# greenhouse_MA_2.net
KiCad netlist of a schematic drawn in Altium Designer
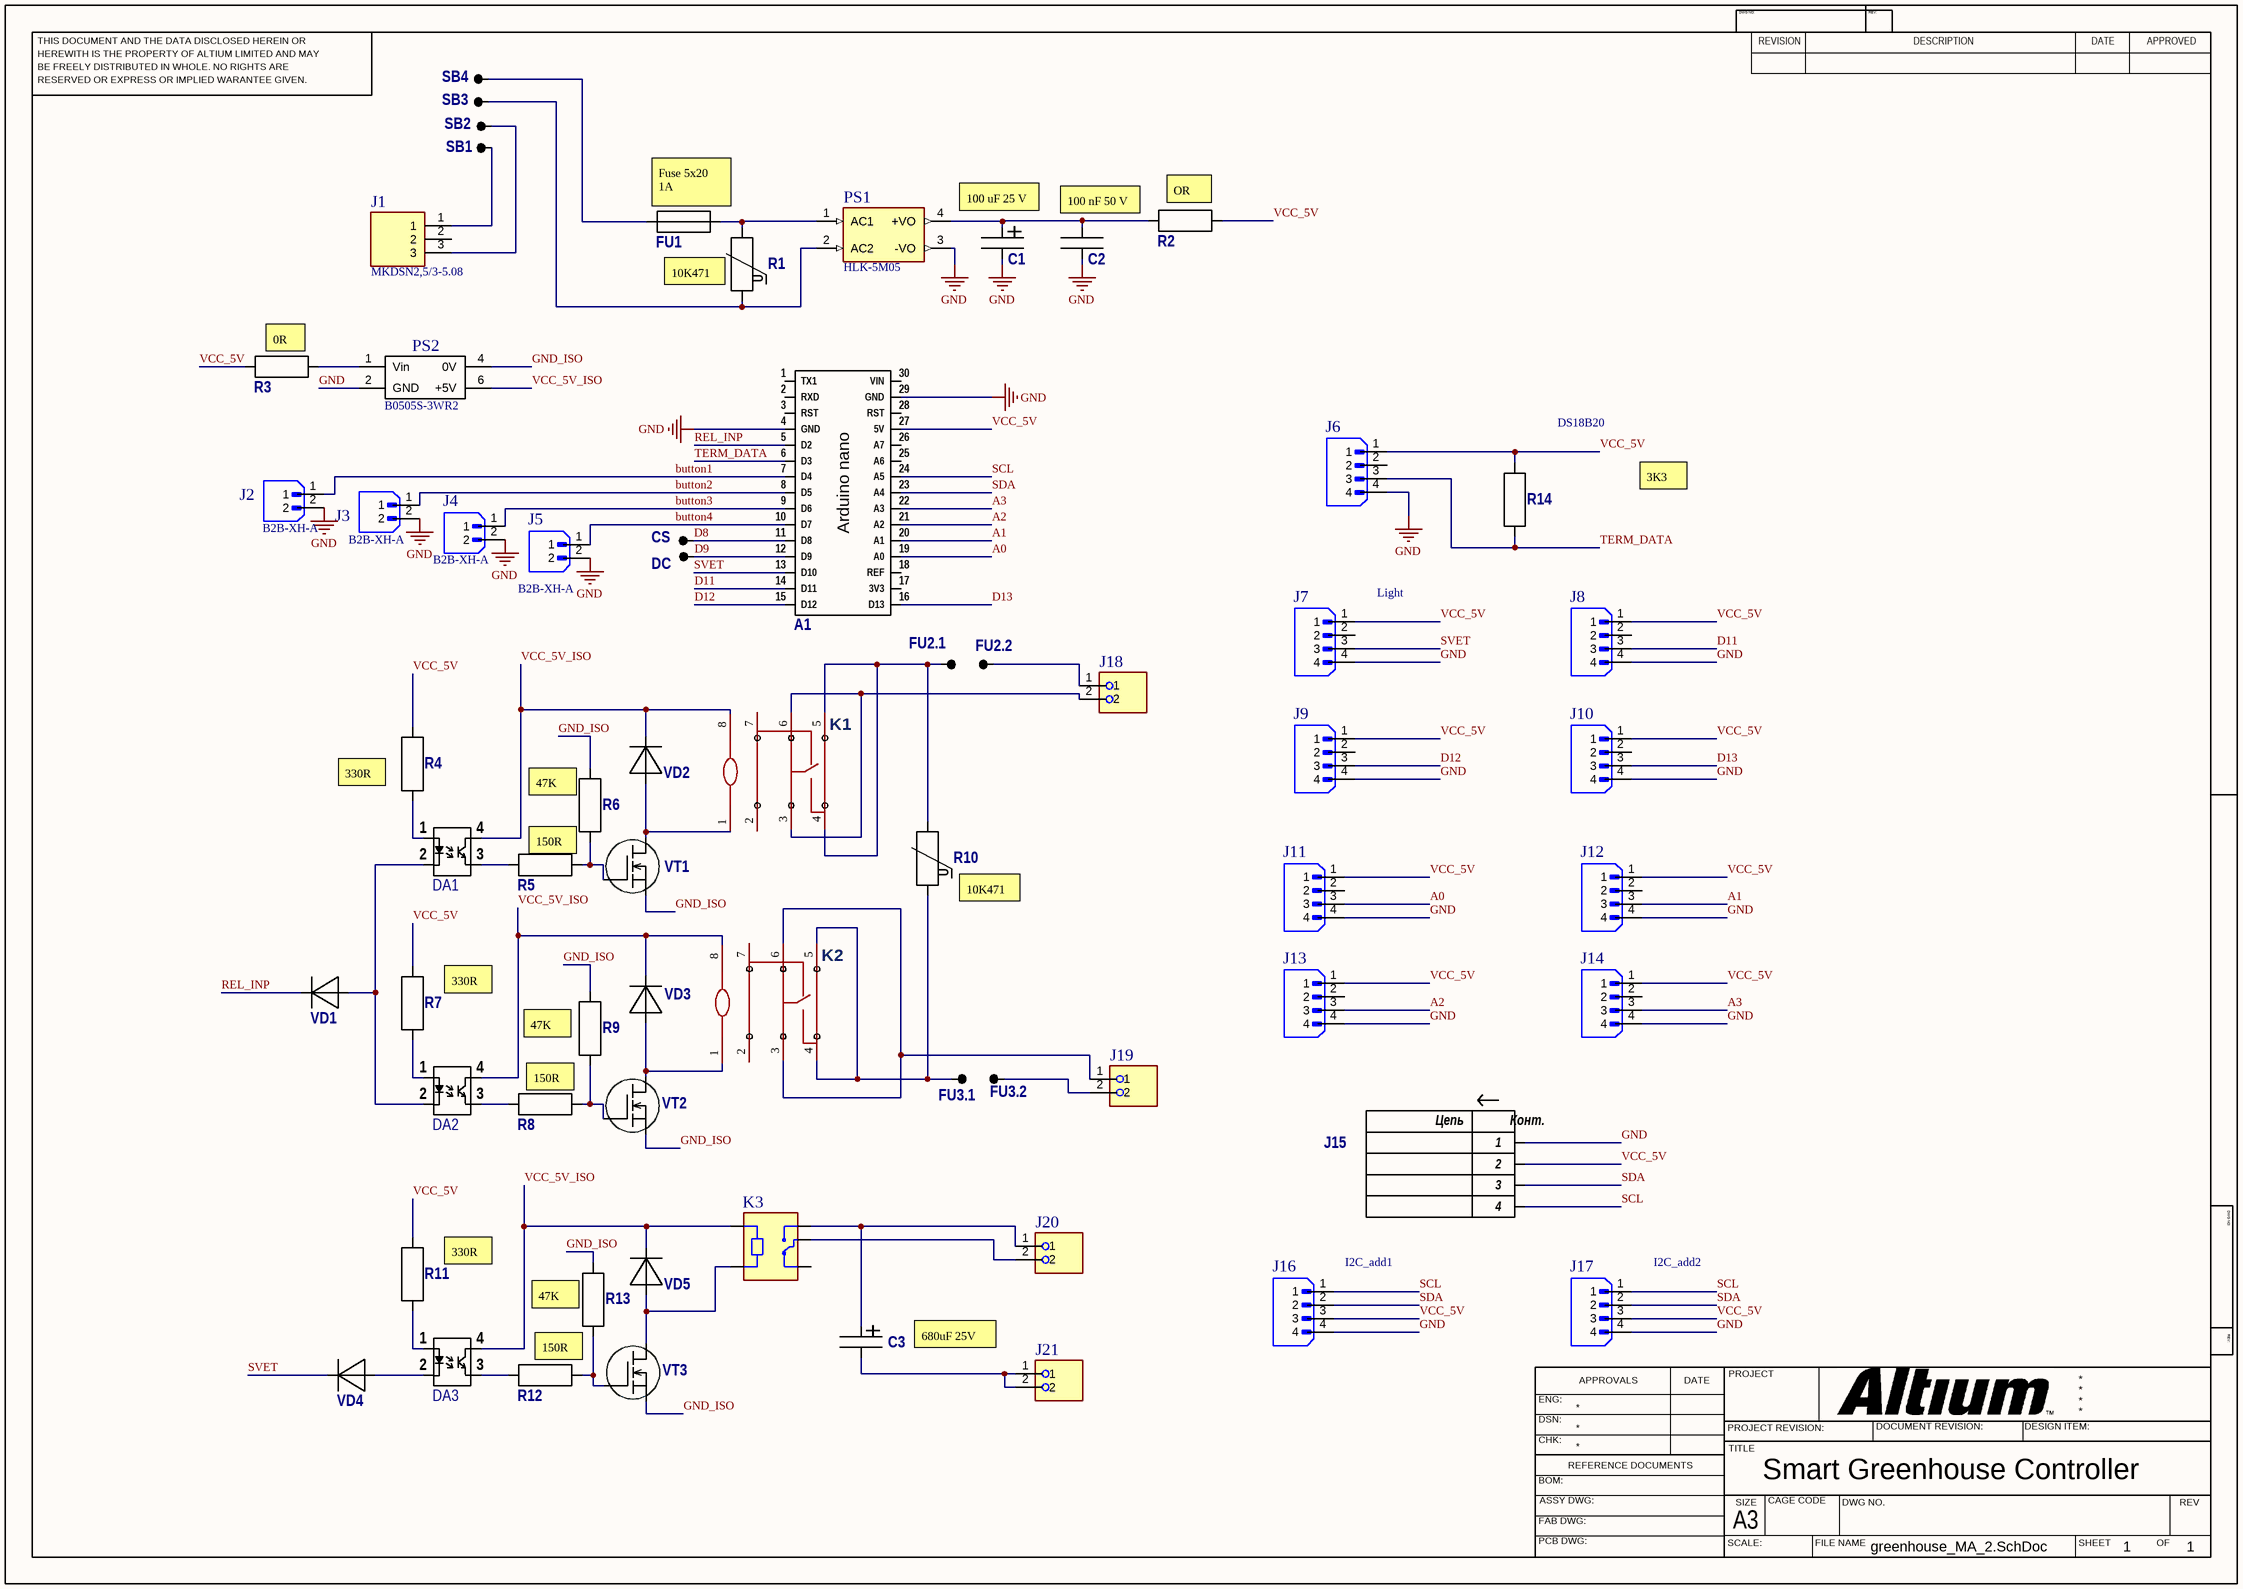
[diagram p0: greenhouse_MA_2.SchDoc]

(export (version "E")
  (design (tool "Eeschema 10.0.6"))
  (components
    (comp (ref "A1")
      (value "Arduino Nano")
      (footprint "Arduino nano")
      (libsource (lib "Microcontroller_V3.4_BVI") (part "Arduino Nano"))
    )
    (comp (ref "C1")
      (value "100uF 25V Electrolytic Capacitor THT Radial")
      (footprint "capr- 2.5D6.5H12")
      (description "Конденсатор алюминиевый радиальный")
      (libsource (lib "RLC V7.1_BVI") (part "C Al R"))
    )
    (comp (ref "C2")
      (value "100nF 50V X7R THT 5mm")
      (footprint "C__s 5-d 5.5-t4")
      (description "Конденсатор керамика")
      (libsource (lib "RLC V7.1_BVI") (part "C_Disk"))
    )
    (comp (ref "C3")
      (value "680uF 25V Electrolytic Capacitor THT Radial")
      (footprint "capr- 3.5D8H20")
      (description "Конденсатор алюминиевый радиальный")
      (libsource (lib "RLC V7.1_BVI") (part "C Al R"))
    )
    (comp (ref "CS")
      (value "Отпайка")
      (footprint "Отпайка 0,5")
      (description "Отпайка для проводника")
      (libsource (lib "RLC V7.1_BVI") (part "Отпайка"))
    )
    (comp (ref "DA1")
      (value "Optocoupler EL817 DIP-4")
      (footprint "DIP-4")
      (description "Оптрон выход - транзистор")
      (libsource (lib "Optocoupler V2.2_BVI") (part "EL817"))
    )
    (comp (ref "DA2")
      (value "Optocoupler EL817 DIP-4")
      (footprint "DIP-4")
      (description "Оптрон выход - транзистор")
      (libsource (lib "Optocoupler V2.2_BVI") (part "EL817"))
    )
    (comp (ref "DA3")
      (value "Optocoupler EL817 DIP-4")
      (footprint "DIP-4")
      (description "Оптрон выход - транзистор")
      (libsource (lib "Optocoupler V2.2_BVI") (part "EL817"))
    )
    (comp (ref "DC")
      (value "Отпайка")
      (footprint "Отпайка 0,5")
      (description "Отпайка для проводника")
      (libsource (lib "RLC V7.1_BVI") (part "Отпайка"))
    )
    (comp (ref "FU1")
      (value "1A slow 5x20 mm")
      (footprint "FU_FC-001-N(DH)")
      (description "Предохранитель плавкий с держателем.")
      (libsource (lib "RLC V7.1_BVI") (part "FU + Clip"))
    )
    (comp (ref "FU2.1")
      (value "Отпайка")
      (footprint "Отпайка 1.5")
      (description "Отпайка для проводника")
      (libsource (lib "RLC V7.1_BVI") (part "Отпайка"))
    )
    (comp (ref "FU2.2")
      (value "Отпайка")
      (footprint "Отпайка 1.5")
      (description "Отпайка для проводника")
      (libsource (lib "RLC V7.1_BVI") (part "Отпайка"))
    )
    (comp (ref "FU3.1")
      (value "Отпайка")
      (footprint "Отпайка 1.5")
      (description "Отпайка для проводника")
      (libsource (lib "RLC V7.1_BVI") (part "Отпайка"))
    )
    (comp (ref "FU3.2")
      (value "Отпайка")
      (footprint "Отпайка 1.5")
      (description "Отпайка для проводника")
      (libsource (lib "RLC V7.1_BVI") (part "Отпайка"))
    )
    (comp (ref "J1")
      (value "MKDSN2,5/3-5.08")
      (footprint "PHOENIX_MKDSN2,5/3-5.08")
      (fields (field (name "MF") "Phoenix Contact"))
      (libsource (lib "MKDSN2_5_3-5.08") (part "MKDSN2,5/3-5.08"))
    )
    (comp (ref "J2")
      (value "B2B-XH-A")
      (footprint "JST_B2B-XH-A")
      (fields (field (name "MF") "{'manufacturer': u'JST Sales America Inc.'}"))
      (libsource (lib "B2B-XH-A") (part "B2B-XH-A"))
    )
    (comp (ref "J3")
      (value "B2B-XH-A")
      (footprint "JST_B2B-XH-A")
      (fields (field (name "MF") "{'manufacturer': u'JST Sales America Inc.'}"))
      (libsource (lib "B2B-XH-A") (part "B2B-XH-A"))
    )
    (comp (ref "J4")
      (value "B2B-XH-A")
      (footprint "JST_B2B-XH-A")
      (fields (field (name "MF") "{'manufacturer': u'JST Sales America Inc.'}"))
      (libsource (lib "B2B-XH-A") (part "B2B-XH-A"))
    )
    (comp (ref "J5")
      (value "B2B-XH-A")
      (footprint "JST_B2B-XH-A")
      (fields (field (name "MF") "{'manufacturer': u'JST Sales America Inc.'}"))
      (libsource (lib "B2B-XH-A") (part "B2B-XH-A"))
    )
    (comp (ref "J6")
      (value "JST B4B-XH-A Connector 1x4 2.5mm THT Vertical")
      (footprint "JST_B4B-XH-A")
      (description "Connector Header Through Hole 4 position 0.098 (2.50mm)")
      (fields (field (name "MF") "JST Sales") (field (name "MP") "B4B-XH-A"))
      (libsource (lib "B4B-XH-A") (part "B4B-XH-A"))
    )
    (comp (ref "J7")
      (value "JST B4B-XH-A Connector 1x4 2.5mm THT Vertical")
      (footprint "JST_B4B-XH-A")
      (description "Connector Header Through Hole 4 position 0.098 (2.50mm)")
      (fields (field (name "MF") "JST Sales") (field (name "MP") "B4B-XH-A"))
      (libsource (lib "B4B-XH-A") (part "B4B-XH-A"))
    )
    (comp (ref "J8")
      (value "JST B4B-XH-A Connector 1x4 2.5mm THT Vertical")
      (footprint "JST_B4B-XH-A")
      (description "Connector Header Through Hole 4 position 0.098 (2.50mm)")
      (fields (field (name "MF") "JST Sales") (field (name "MP") "B4B-XH-A"))
      (libsource (lib "B4B-XH-A") (part "B4B-XH-A"))
    )
    (comp (ref "J9")
      (value "JST B4B-XH-A Connector 1x4 2.5mm THT Vertical")
      (footprint "JST_B4B-XH-A")
      (description "Connector Header Through Hole 4 position 0.098 (2.50mm)")
      (fields (field (name "MF") "JST Sales") (field (name "MP") "B4B-XH-A"))
      (libsource (lib "B4B-XH-A") (part "B4B-XH-A"))
    )
    (comp (ref "J10")
      (value "JST B4B-XH-A Connector 1x4 2.5mm THT Vertical")
      (footprint "JST_B4B-XH-A")
      (description "Connector Header Through Hole 4 position 0.098 (2.50mm)")
      (fields (field (name "MF") "JST Sales") (field (name "MP") "B4B-XH-A"))
      (libsource (lib "B4B-XH-A") (part "B4B-XH-A"))
    )
    (comp (ref "J11")
      (value "JST B4B-XH-A Connector 1x4 2.5mm THT Vertical")
      (footprint "JST_B4B-XH-A")
      (description "Connector Header Through Hole 4 position 0.098 (2.50mm)")
      (fields (field (name "MF") "JST Sales") (field (name "MP") "B4B-XH-A"))
      (libsource (lib "B4B-XH-A") (part "B4B-XH-A"))
    )
    (comp (ref "J12")
      (value "JST B4B-XH-A Connector 1x4 2.5mm THT Vertical")
      (footprint "JST_B4B-XH-A")
      (description "Connector Header Through Hole 4 position 0.098 (2.50mm)")
      (fields (field (name "MF") "JST Sales") (field (name "MP") "B4B-XH-A"))
      (libsource (lib "B4B-XH-A") (part "B4B-XH-A"))
    )
    (comp (ref "J13")
      (value "JST B4B-XH-A Connector 1x4 2.5mm THT Vertical")
      (footprint "JST_B4B-XH-A")
      (description "Connector Header Through Hole 4 position 0.098 (2.50mm)")
      (fields (field (name "MF") "JST Sales") (field (name "MP") "B4B-XH-A"))
      (libsource (lib "B4B-XH-A") (part "B4B-XH-A"))
    )
    (comp (ref "J14")
      (value "JST B4B-XH-A Connector 1x4 2.5mm THT Vertical")
      (footprint "JST_B4B-XH-A")
      (description "Connector Header Through Hole 4 position 0.098 (2.50mm)")
      (fields (field (name "MF") "JST Sales") (field (name "MP") "B4B-XH-A"))
      (libsource (lib "B4B-XH-A") (part "B4B-XH-A"))
    )
    (comp (ref "J15")
      (value "Pin Header 1x4 2.54mm Right Angle THT Male")
      (footprint "KLS1-207-1*04 R")
      (description "Разъём штыревой на плату 2.54мм 1х4 pin")
      (libsource (lib "Connectors V8.3_BVI") (part "Штырь 1* 4  (1)"))
    )
    (comp (ref "J16")
      (value "JST B4B-XH-A Connector 1x4 2.5mm THT Vertical")
      (footprint "JST_B4B-XH-A")
      (description "Connector Header Through Hole 4 position 0.098 (2.50mm)")
      (fields (field (name "MF") "JST Sales") (field (name "MP") "B4B-XH-A"))
      (libsource (lib "B4B-XH-A") (part "B4B-XH-A"))
    )
    (comp (ref "J17")
      (value "JST B4B-XH-A Connector 1x4 2.5mm THT Vertical")
      (footprint "JST_B4B-XH-A")
      (description "Connector Header Through Hole 4 position 0.098 (2.50mm)")
      (fields (field (name "MF") "JST Sales") (field (name "MP") "B4B-XH-A"))
      (libsource (lib "B4B-XH-A") (part "B4B-XH-A"))
    )
    (comp (ref "J18")
      (value "Phoenix Contact MKDSN 2,5/2-5.08 Terminal Block 1x2 5.08mm THT")
      (footprint "PHOENIX_1729128")
      (fields (field (name "MF") "Phoenix Contact") (field (name "MP") "1729128"))
      (libsource (lib "MKDSN2_5_2-5.08") (part "1729128"))
    )
    (comp (ref "J19")
      (value "Phoenix Contact MKDSN 2,5/2-5.08 Terminal Block 1x2 5.08mm THT")
      (footprint "PHOENIX_1729128")
      (fields (field (name "MF") "Phoenix Contact") (field (name "MP") "1729128"))
      (libsource (lib "MKDSN2_5_2-5.08") (part "1729128"))
    )
    (comp (ref "J20")
      (value "Phoenix Contact MKDSN 2,5/2-5.08 Terminal Block 1x2 5.08mm THT")
      (footprint "PHOENIX_1729128")
      (fields (field (name "MF") "Phoenix Contact") (field (name "MP") "1729128"))
      (libsource (lib "MKDSN2_5_2-5.08") (part "1729128"))
    )
    (comp (ref "J21")
      (value "Phoenix Contact MKDSN 2,5/2-5.08 Terminal Block 1x2 5.08mm THT")
      (footprint "PHOENIX_1729128")
      (fields (field (name "MF") "Phoenix Contact") (field (name "MP") "1729128"))
      (libsource (lib "MKDSN2_5_2-5.08") (part "1729128"))
    )
    (comp (ref "K1")
      (value "Relay SMIH-05VDC-SL-C 5V 16A THT")
      (footprint "SMIH-5VDC-SL-C")
      (fields (field (name "MANUFACTURER") "松乐") (field (name "MANUFACTURER PART") "SMIH-05VDC-SL-C"))
      (libsource (lib "SMIH-5VDC-SL-C") (part "SMIH-05VDC-SL-C"))
    )
    (comp (ref "K2")
      (value "Relay SMIH-05VDC-SL-C 5V 16A THT")
      (footprint "SMIH-5VDC-SL-C")
      (fields (field (name "MANUFACTURER") "松乐") (field (name "MANUFACTURER PART") "SMIH-05VDC-SL-C"))
      (libsource (lib "SMIH-5VDC-SL-C") (part "SMIH-05VDC-SL-C"))
    )
    (comp (ref "K3")
      (value "Relay SRD-05VDC-SL-C 5V 10A THT")
      (footprint "RELAY_SRD-05VDC-SL-C")
      (fields (field (name "MF") "Songle Relay") (field (name "MP") "SRD-05VDC-SL-C"))
      (libsource (lib "SRD-05VDC-SL-C") (part "SRD-05VDC-SL-C"))
    )
    (comp (ref "PS1")
      (value "HLK-5M05")
      (footprint "CONV_HLK-5M05")
      (description "AC DC 220V to 5V 5W 5Watt Isolated Switching Step-Down Power Supply Module Converter")
      (fields (field (name "MF") "Hi-link"))
      (libsource (lib "HLK-5M05") (part "HLK-5M05"))
    )
    (comp (ref "PS2")
      (value "B0505S-3WR2")
      (footprint "B0505S-2W")
      (description "Изолированный DC-DC преобразователь, вход 5В, выход 5В 3Вт")
      (libsource (lib "B0505S-2W") (part "B0505S-2W"))
    )
    (comp (ref "R1")
      (value "10K471")
      (footprint "var 10D (Т-5мм)")
      (description "Варистор")
      (libsource (lib "") (part "RU_1_1"))
    )
    (comp (ref "R2")
      (value "0R 1% 1206")
      (footprint "Res_1206 3D")
      (description "Резисторы плёночные (SMD; МЛТ; С2-33Н; MP9xxx)")
      (libsource (lib "RLC V7.1_BVI") (part "R"))
    )
    (comp (ref "R3")
      (value "0R 1% 1206")
      (footprint "Res_1206 3D")
      (description "Резисторы плёночные (SMD; МЛТ; С2-33Н; MP9xxx)")
      (libsource (lib "RLC V7.1_BVI") (part "R"))
    )
    (comp (ref "R4")
      (value "330R 1% 1206")
      (footprint "Res_1206 3D")
      (description "Резисторы плёночные (SMD; МЛТ; С2-33Н; MP9xxx)")
      (libsource (lib "RLC V7.1_BVI") (part "R"))
    )
    (comp (ref "R5")
      (value "150R 1% 1206")
      (footprint "Res_1206 3D")
      (description "Резисторы плёночные (SMD; МЛТ; С2-33Н; MP9xxx)")
      (libsource (lib "RLC V7.1_BVI") (part "R"))
    )
    (comp (ref "R6")
      (value "47k 1% 1206")
      (footprint "Res_1206 3D")
      (description "Резисторы плёночные (SMD; МЛТ; С2-33Н; MP9xxx)")
      (libsource (lib "RLC V7.1_BVI") (part "R"))
    )
    (comp (ref "R7")
      (value "330R 1% 1206")
      (footprint "Res_1206 3D")
      (description "Резисторы плёночные (SMD; МЛТ; С2-33Н; MP9xxx)")
      (libsource (lib "RLC V7.1_BVI") (part "R"))
    )
    (comp (ref "R8")
      (value "150R 1% 1206")
      (footprint "Res_1206 3D")
      (description "Резисторы плёночные (SMD; МЛТ; С2-33Н; MP9xxx)")
      (libsource (lib "RLC V7.1_BVI") (part "R"))
    )
    (comp (ref "R9")
      (value "47k 1% 1206")
      (footprint "Res_1206 3D")
      (description "Резисторы плёночные (SMD; МЛТ; С2-33Н; MP9xxx)")
      (libsource (lib "RLC V7.1_BVI") (part "R"))
    )
    (comp (ref "R10")
      (value "10K471")
      (footprint "var 10D (Т-5мм)")
      (description "Варистор")
      (libsource (lib "RLC V7.1_BVI") (part "RU_1"))
    )
    (comp (ref "R11")
      (value "330R 1% 1206")
      (footprint "Res_1206 3D")
      (description "Резисторы плёночные (SMD; МЛТ; С2-33Н; MP9xxx)")
      (libsource (lib "RLC V7.1_BVI") (part "R"))
    )
    (comp (ref "R12")
      (value "150R 1% 1206")
      (footprint "Res_1206 3D")
      (description "Резисторы плёночные (SMD; МЛТ; С2-33Н; MP9xxx)")
      (libsource (lib "RLC V7.1_BVI") (part "R"))
    )
    (comp (ref "R13")
      (value "47k 1% 1206")
      (footprint "Res_1206 3D")
      (description "Резисторы плёночные (SMD; МЛТ; С2-33Н; MP9xxx)")
      (libsource (lib "RLC V7.1_BVI") (part "R"))
    )
    (comp (ref "R14")
      (value "3.3K 1% 1206")
      (footprint "Res_1206 3D")
      (description "Резисторы плёночные (SMD; МЛТ; С2-33Н; MP9xxx)")
      (libsource (lib "RLC V7.1_BVI") (part "R"))
    )
    (comp (ref "SB1")
      (value "Отпайка")
      (footprint "Отпайка 1.2")
      (description "Отпайка для проводника")
      (libsource (lib "Switches V3.4_BVI") (part "Отпайка"))
    )
    (comp (ref "SB2")
      (value "Отпайка")
      (footprint "Отпайка 1.2")
      (description "Отпайка для проводника")
      (libsource (lib "Switches V3.4_BVI") (part "Отпайка"))
    )
    (comp (ref "SB3")
      (value "Отпайка")
      (footprint "Отпайка 1.2")
      (description "Отпайка для проводника")
      (libsource (lib "Switches V3.4_BVI") (part "Отпайка"))
    )
    (comp (ref "SB4")
      (value "Отпайка")
      (footprint "Отпайка 1.2")
      (description "Отпайка для проводника")
      (libsource (lib "Switches V3.4_BVI") (part "Отпайка"))
    )
    (comp (ref "VD1")
      (value "1N4007 1A 1000V Rectifier Diode DO-41")
      (footprint "DO-41  (5.0)")
      (description "Диод  одиночный")
      (libsource (lib "VD_VT_V6.3 BVI") (part "Диод.  x1  (2)"))
    )
    (comp (ref "VD2")
      (value "UF4007 1A 1000V Fast Diode DO-41")
      (footprint "DO-41  (5.0)")
      (description "Диод  одиночный")
      (libsource (lib "VD_VT_V6.3 BVI") (part "Диод.  x1  (2)"))
    )
    (comp (ref "VD3")
      (value "UF4007 1A 1000V Fast Diode DO-41")
      (footprint "DO-41  (5.0)")
      (description "Диод  одиночный")
      (libsource (lib "VD_VT_V6.3 BVI") (part "Диод.  x1  (2)"))
    )
    (comp (ref "VD4")
      (value "1N4007 1A 1000V Rectifier Diode DO-41")
      (footprint "DO-41  (5.0)")
      (description "Диод  одиночный")
      (libsource (lib "VD_VT_V6.3 BVI") (part "Диод.  x1  (2)"))
    )
    (comp (ref "VD5")
      (value "UF4007 1A 1000V Fast Diode DO-41")
      (footprint "DO-41  (5.0)")
      (description "Диод  одиночный")
      (libsource (lib "VD_VT_V6.3 BVI") (part "Диод.  x1  (2)"))
    )
    (comp (ref "VT1")
      (value "IRLML6344")
      (footprint "SOT-23-3")
      (description "Транзистор MOSFET N-канал")
      (libsource (lib "VD_VT_V6.3 BVI") (part "VT MOSFET-N"))
    )
    (comp (ref "VT2")
      (value "IRLML6344")
      (footprint "SOT-23-3")
      (description "Транзистор MOSFET N-канал")
      (libsource (lib "VD_VT_V6.3 BVI") (part "VT MOSFET-N"))
    )
    (comp (ref "VT3")
      (value "IRLML6344")
      (footprint "SOT-23-3")
      (description "Транзистор MOSFET N-канал")
      (libsource (lib "VD_VT_V6.3 BVI") (part "VT MOSFET-N"))
    )
  )
  (nets
    (net (code "1") (name "/A0") (class "Default")
      (node (ref "A1") (pin "19") (pinfunction "A0_19") (pintype "passive"))
      (node (ref "J11") (pin "3") (pinfunction "3_3") (pintype "passive"))
    )
    (net (code "2") (name "/A1") (class "Default")
      (node (ref "A1") (pin "20") (pinfunction "A1_20") (pintype "passive"))
      (node (ref "J12") (pin "3") (pinfunction "3_3") (pintype "passive"))
    )
    (net (code "3") (name "/A2") (class "Default")
      (node (ref "A1") (pin "21") (pinfunction "A2_21") (pintype "passive"))
      (node (ref "J13") (pin "3") (pinfunction "3_3") (pintype "passive"))
    )
    (net (code "4") (name "/A3") (class "Default")
      (node (ref "A1") (pin "22") (pinfunction "A3_22") (pintype "passive"))
      (node (ref "J14") (pin "3") (pinfunction "3_3") (pintype "passive"))
    )
    (net (code "5") (name "/D8") (class "Default")
      (node (ref "A1") (pin "11") (pinfunction "D8_11") (pintype "passive"))
      (node (ref "CS") (pin "1") (pintype "passive"))
    )
    (net (code "6") (name "/D9") (class "Default")
      (node (ref "A1") (pin "12") (pinfunction "D9_12") (pintype "passive"))
      (node (ref "DC") (pin "1") (pintype "passive"))
    )
    (net (code "7") (name "/D11") (class "Default")
      (node (ref "A1") (pin "14") (pinfunction "D11_14") (pintype "passive"))
      (node (ref "J8") (pin "3") (pinfunction "3_3") (pintype "passive"))
    )
    (net (code "8") (name "/D12") (class "Default")
      (node (ref "A1") (pin "15") (pinfunction "D12_15") (pintype "passive"))
      (node (ref "J9") (pin "3") (pinfunction "3_3") (pintype "passive"))
    )
    (net (code "9") (name "/D13") (class "Default")
      (node (ref "A1") (pin "16") (pinfunction "D13_16") (pintype "passive"))
      (node (ref "J10") (pin "3") (pinfunction "3_3") (pintype "passive"))
    )
    (net (code "10") (name "/GND_ISO") (class "Default")
      (node (ref "PS2") (pin "4") (pinfunction "0V_4") (pintype "passive"))
      (node (ref "R13") (pin "2") (pintype "passive"))
      (node (ref "R6") (pin "2") (pintype "passive"))
      (node (ref "R9") (pin "2") (pintype "passive"))
      (node (ref "VT1") (pin "3") (pinfunction "S_3") (pintype "passive"))
      (node (ref "VT2") (pin "3") (pinfunction "S_3") (pintype "passive"))
      (node (ref "VT3") (pin "3") (pinfunction "S_3") (pintype "passive"))
    )
    (net (code "11") (name "/REL_INP") (class "Default")
      (node (ref "A1") (pin "5") (pinfunction "D2_5") (pintype "passive"))
      (node (ref "VD1") (pin "1") (pinfunction "K_1") (pintype "passive"))
    )
    (net (code "12") (name "/SCL") (class "Default")
      (node (ref "A1") (pin "24") (pinfunction "A5_24") (pintype "passive"))
      (node (ref "J15") (pin "4") (pintype "passive"))
      (node (ref "J16") (pin "1") (pinfunction "1_1") (pintype "passive"))
      (node (ref "J17") (pin "1") (pinfunction "1_1") (pintype "passive"))
    )
    (net (code "13") (name "/SDA") (class "Default")
      (node (ref "A1") (pin "23") (pinfunction "A4_23") (pintype "passive"))
      (node (ref "J15") (pin "3") (pintype "passive"))
      (node (ref "J16") (pin "2") (pinfunction "2_2") (pintype "passive"))
      (node (ref "J17") (pin "2") (pinfunction "2_2") (pintype "passive"))
    )
    (net (code "14") (name "/SVET") (class "Default")
      (node (ref "A1") (pin "13") (pinfunction "D10_13") (pintype "passive"))
      (node (ref "J7") (pin "3") (pinfunction "3_3") (pintype "passive"))
      (node (ref "VD4") (pin "1") (pinfunction "K_1") (pintype "passive"))
    )
    (net (code "15") (name "/TERM_DATA") (class "Default")
      (node (ref "A1") (pin "6") (pinfunction "D3_6") (pintype "passive"))
      (node (ref "J6") (pin "3") (pinfunction "3_3") (pintype "passive"))
      (node (ref "R14") (pin "1") (pintype "passive"))
    )
    (net (code "16") (name "/VCC_5V") (class "Default")
      (node (ref "A1") (pin "27") (pinfunction "5V_27") (pintype "passive"))
      (node (ref "J10") (pin "1") (pinfunction "1_1") (pintype "passive"))
      (node (ref "J11") (pin "1") (pinfunction "1_1") (pintype "passive"))
      (node (ref "J12") (pin "1") (pinfunction "1_1") (pintype "passive"))
      (node (ref "J13") (pin "1") (pinfunction "1_1") (pintype "passive"))
      (node (ref "J14") (pin "1") (pinfunction "1_1") (pintype "passive"))
      (node (ref "J15") (pin "2") (pintype "passive"))
      (node (ref "J16") (pin "3") (pinfunction "3_3") (pintype "passive"))
      (node (ref "J17") (pin "3") (pinfunction "3_3") (pintype "passive"))
      (node (ref "J6") (pin "1") (pinfunction "1_1") (pintype "passive"))
      (node (ref "J7") (pin "1") (pinfunction "1_1") (pintype "passive"))
      (node (ref "J8") (pin "1") (pinfunction "1_1") (pintype "passive"))
      (node (ref "J9") (pin "1") (pinfunction "1_1") (pintype "passive"))
      (node (ref "R11") (pin "2") (pintype "passive"))
      (node (ref "R14") (pin "2") (pintype "passive"))
      (node (ref "R2") (pin "1") (pintype "passive"))
      (node (ref "R3") (pin "2") (pintype "passive"))
      (node (ref "R4") (pin "2") (pintype "passive"))
      (node (ref "R7") (pin "2") (pintype "passive"))
    )
    (net (code "17") (name "/VCC_5V_ISO") (class "Default")
      (node (ref "DA1") (pin "4") (pinfunction "C_4") (pintype "passive"))
      (node (ref "DA2") (pin "4") (pinfunction "C_4") (pintype "passive"))
      (node (ref "DA3") (pin "4") (pinfunction "C_4") (pintype "passive"))
      (node (ref "K1") (pin "8") (pinfunction "8_8") (pintype "passive"))
      (node (ref "K2") (pin "8") (pinfunction "8_8") (pintype "passive"))
      (node (ref "K3") (pin "A1") (pinfunction "A1_A1") (pintype "passive"))
      (node (ref "PS2") (pin "6") (pinfunction "+5V_6") (pintype "passive"))
      (node (ref "VD2") (pin "1") (pinfunction "K_1") (pintype "passive"))
      (node (ref "VD3") (pin "1") (pinfunction "K_1") (pintype "passive"))
      (node (ref "VD5") (pin "1") (pinfunction "K_1") (pintype "passive"))
    )
    (net (code "18") (name "/button1") (class "Default")
      (node (ref "A1") (pin "7") (pinfunction "D4_7") (pintype "passive"))
      (node (ref "J2") (pin "1") (pinfunction "1_1") (pintype "passive"))
    )
    (net (code "19") (name "/button2") (class "Default")
      (node (ref "A1") (pin "8") (pinfunction "D5_8") (pintype "passive"))
      (node (ref "J3") (pin "1") (pinfunction "1_1") (pintype "passive"))
    )
    (net (code "20") (name "/button3") (class "Default")
      (node (ref "A1") (pin "9") (pinfunction "D6_9") (pintype "passive"))
      (node (ref "J4") (pin "1") (pinfunction "1_1") (pintype "passive"))
    )
    (net (code "21") (name "/button4") (class "Default")
      (node (ref "A1") (pin "10") (pinfunction "D7_10") (pintype "passive"))
      (node (ref "J5") (pin "1") (pinfunction "1_1") (pintype "passive"))
    )
    (net (code "22") (name "GND") (class "Default")
      (node (ref "A1") (pin "29") (pinfunction "GND_29") (pintype "passive"))
      (node (ref "A1") (pin "4") (pinfunction "GND_4") (pintype "passive"))
      (node (ref "C1") (pin "1") (pinfunction "-_1") (pintype "passive"))
      (node (ref "C2") (pin "2") (pintype "passive"))
      (node (ref "J10") (pin "4") (pinfunction "4_4") (pintype "passive"))
      (node (ref "J11") (pin "4") (pinfunction "4_4") (pintype "passive"))
      (node (ref "J12") (pin "4") (pinfunction "4_4") (pintype "passive"))
      (node (ref "J13") (pin "4") (pinfunction "4_4") (pintype "passive"))
      (node (ref "J14") (pin "4") (pinfunction "4_4") (pintype "passive"))
      (node (ref "J15") (pin "1") (pintype "passive"))
      (node (ref "J16") (pin "4") (pinfunction "4_4") (pintype "passive"))
      (node (ref "J17") (pin "4") (pinfunction "4_4") (pintype "passive"))
      (node (ref "J2") (pin "2") (pinfunction "2_2") (pintype "passive"))
      (node (ref "J3") (pin "2") (pinfunction "2_2") (pintype "passive"))
      (node (ref "J4") (pin "2") (pinfunction "2_2") (pintype "passive"))
      (node (ref "J5") (pin "2") (pinfunction "2_2") (pintype "passive"))
      (node (ref "J6") (pin "4") (pinfunction "4_4") (pintype "passive"))
      (node (ref "J7") (pin "4") (pinfunction "4_4") (pintype "passive"))
      (node (ref "J8") (pin "4") (pinfunction "4_4") (pintype "passive"))
      (node (ref "J9") (pin "4") (pinfunction "4_4") (pintype "passive"))
      (node (ref "PS1") (pin "3") (pinfunction "-VO_3") (pintype "output"))
      (node (ref "PS2") (pin "2") (pinfunction "GND_2") (pintype "passive"))
    )
    (net (code "23") (name "Net-(C1-+)") (class "Default")
      (node (ref "C1") (pin "2") (pinfunction "+_2") (pintype "passive"))
      (node (ref "C2") (pin "1") (pintype "passive"))
      (node (ref "PS1") (pin "4") (pinfunction "+VO_4") (pintype "output"))
      (node (ref "R2") (pin "2") (pintype "passive"))
    )
    (net (code "24") (name "Net-(C3-+)") (class "Default")
      (node (ref "C3") (pin "2") (pinfunction "+_2") (pintype "passive"))
      (node (ref "J20") (pin "1") (pinfunction "1_1") (pintype "passive"))
      (node (ref "K3") (pin "NO") (pinfunction "NO_NO") (pintype "passive"))
    )
    (net (code "25") (name "Net-(C3--)") (class "Default")
      (node (ref "C3") (pin "1") (pinfunction "-_1") (pintype "passive"))
      (node (ref "J21") (pin "1") (pinfunction "1_1") (pintype "passive"))
      (node (ref "J21") (pin "2") (pinfunction "2_2") (pintype "passive"))
    )
    (net (code "26") (name "Net-(DA1-E)") (class "Default")
      (node (ref "DA1") (pin "3") (pinfunction "E_3") (pintype "passive"))
      (node (ref "R5") (pin "1") (pintype "passive"))
    )
    (net (code "27") (name "Net-(DA1-Led_A)") (class "Default")
      (node (ref "DA1") (pin "1") (pinfunction "Led_A_1") (pintype "passive"))
      (node (ref "R4") (pin "1") (pintype "passive"))
    )
    (net (code "28") (name "Net-(DA1-Led_C)") (class "Default")
      (node (ref "DA1") (pin "2") (pinfunction "Led_C_2") (pintype "passive"))
      (node (ref "DA2") (pin "2") (pinfunction "Led_C_2") (pintype "passive"))
      (node (ref "VD1") (pin "2") (pinfunction "A_2") (pintype "passive"))
    )
    (net (code "29") (name "Net-(DA2-E)") (class "Default")
      (node (ref "DA2") (pin "3") (pinfunction "E_3") (pintype "passive"))
      (node (ref "R8") (pin "1") (pintype "passive"))
    )
    (net (code "30") (name "Net-(DA2-Led_A)") (class "Default")
      (node (ref "DA2") (pin "1") (pinfunction "Led_A_1") (pintype "passive"))
      (node (ref "R7") (pin "1") (pintype "passive"))
    )
    (net (code "31") (name "Net-(DA3-E)") (class "Default")
      (node (ref "DA3") (pin "3") (pinfunction "E_3") (pintype "passive"))
      (node (ref "R12") (pin "1") (pintype "passive"))
    )
    (net (code "32") (name "Net-(DA3-Led_A)") (class "Default")
      (node (ref "DA3") (pin "1") (pinfunction "Led_A_1") (pintype "passive"))
      (node (ref "R11") (pin "1") (pintype "passive"))
    )
    (net (code "33") (name "Net-(DA3-Led_C)") (class "Default")
      (node (ref "DA3") (pin "2") (pinfunction "Led_C_2") (pintype "passive"))
      (node (ref "VD4") (pin "2") (pinfunction "A_2") (pintype "passive"))
    )
    (net (code "34") (name "Net-(FU1-Pad1)") (class "Default")
      (node (ref "FU1") (pin "1") (pintype "passive"))
      (node (ref "SB4") (pin "1") (pintype "passive"))
    )
    (net (code "35") (name "Net-(FU2.1-Pad1)") (class "Default")
      (node (ref "FU2.1") (pin "1") (pintype "passive"))
      (node (ref "K1") (pin "4") (pinfunction "4_4") (pintype "passive"))
      (node (ref "K1") (pin "5") (pinfunction "5_5") (pintype "passive"))
      (node (ref "R10") (pin "2") (pintype "passive"))
    )
    (net (code "36") (name "Net-(FU2.2-Pad1)") (class "Default")
      (node (ref "FU2.2") (pin "1") (pintype "passive"))
      (node (ref "J18") (pin "1") (pinfunction "1_1") (pintype "passive"))
    )
    (net (code "37") (name "Net-(FU3.1-Pad1)") (class "Default")
      (node (ref "FU3.1") (pin "1") (pintype "passive"))
      (node (ref "K2") (pin "4") (pinfunction "4_4") (pintype "passive"))
      (node (ref "K2") (pin "5") (pinfunction "5_5") (pintype "passive"))
      (node (ref "R10") (pin "1") (pintype "passive"))
    )
    (net (code "38") (name "Net-(FU3.2-Pad1)") (class "Default")
      (node (ref "FU3.2") (pin "1") (pintype "passive"))
      (node (ref "J19") (pin "2") (pinfunction "2_2") (pintype "passive"))
    )
    (net (code "39") (name "Net-(J1-Pad1)") (class "Default")
      (node (ref "J1") (pin "1") (pinfunction "1_1") (pintype "passive"))
      (node (ref "SB1") (pin "1") (pintype "passive"))
    )
    (net (code "40") (name "Net-(J1-Pad3)") (class "Default")
      (node (ref "J1") (pin "3") (pinfunction "3_3") (pintype "passive"))
      (node (ref "SB2") (pin "1") (pintype "passive"))
    )
    (net (code "41") (name "Net-(J18-Pad2)") (class "Default")
      (node (ref "J18") (pin "2") (pinfunction "2_2") (pintype "passive"))
      (node (ref "K1") (pin "3") (pinfunction "3_3") (pintype "passive"))
      (node (ref "K1") (pin "6") (pinfunction "6_6") (pintype "passive"))
    )
    (net (code "42") (name "Net-(J19-Pad1)") (class "Default")
      (node (ref "J19") (pin "1") (pinfunction "1_1") (pintype "passive"))
      (node (ref "K2") (pin "3") (pinfunction "3_3") (pintype "passive"))
      (node (ref "K2") (pin "6") (pinfunction "6_6") (pintype "passive"))
    )
    (net (code "43") (name "Net-(J20-Pad2)") (class "Default")
      (node (ref "J20") (pin "2") (pinfunction "2_2") (pintype "passive"))
      (node (ref "K3") (pin "COM") (pinfunction "COM_COM") (pintype "passive"))
    )
    (net (code "44") (name "Net-(PS1-AC1)") (class "Default")
      (node (ref "FU1") (pin "2") (pintype "passive"))
      (node (ref "PS1") (pin "1") (pinfunction "AC1_1") (pintype "input"))
      (node (ref "R1") (pin "2") (pintype "passive"))
    )
    (net (code "45") (name "Net-(PS1-AC2)") (class "Default")
      (node (ref "PS1") (pin "2") (pinfunction "AC2_2") (pintype "input"))
      (node (ref "R1") (pin "1") (pintype "passive"))
      (node (ref "SB3") (pin "1") (pintype "passive"))
    )
    (net (code "46") (name "Net-(PS2-Vin)") (class "Default")
      (node (ref "PS2") (pin "1") (pinfunction "Vin_1") (pintype "passive"))
      (node (ref "R3") (pin "1") (pintype "passive"))
    )
    (net (code "47") (name "Net-(VD2-A)") (class "Default")
      (node (ref "K1") (pin "1") (pinfunction "1_1") (pintype "passive"))
      (node (ref "VD2") (pin "2") (pinfunction "A_2") (pintype "passive"))
      (node (ref "VT1") (pin "2") (pinfunction "D_2") (pintype "passive"))
    )
    (net (code "48") (name "Net-(VD3-A)") (class "Default")
      (node (ref "K2") (pin "1") (pinfunction "1_1") (pintype "passive"))
      (node (ref "VD3") (pin "2") (pinfunction "A_2") (pintype "passive"))
      (node (ref "VT2") (pin "2") (pinfunction "D_2") (pintype "passive"))
    )
    (net (code "49") (name "Net-(VD5-A)") (class "Default")
      (node (ref "K3") (pin "A2") (pinfunction "A2_A2") (pintype "passive"))
      (node (ref "VD5") (pin "2") (pinfunction "A_2") (pintype "passive"))
      (node (ref "VT3") (pin "2") (pinfunction "D_2") (pintype "passive"))
    )
    (net (code "50") (name "Net-(VT1-G)") (class "Default")
      (node (ref "R5") (pin "2") (pintype "passive"))
      (node (ref "R6") (pin "1") (pintype "passive"))
      (node (ref "VT1") (pin "1") (pinfunction "G_1") (pintype "passive"))
    )
    (net (code "51") (name "Net-(VT2-G)") (class "Default")
      (node (ref "R8") (pin "2") (pintype "passive"))
      (node (ref "R9") (pin "1") (pintype "passive"))
      (node (ref "VT2") (pin "1") (pinfunction "G_1") (pintype "passive"))
    )
    (net (code "52") (name "Net-(VT3-G)") (class "Default")
      (node (ref "R12") (pin "2") (pintype "passive"))
      (node (ref "R13") (pin "1") (pintype "passive"))
      (node (ref "VT3") (pin "1") (pinfunction "G_1") (pintype "passive"))
    )
    (net (code "53") (name "unconnected-(A1-3V3-Pad17)") (class "Default")
      (node (ref "A1") (pin "17") (pinfunction "3V3_17") (pintype "passive"))
    )
    (net (code "54") (name "unconnected-(A1-A6-Pad25)") (class "Default")
      (node (ref "A1") (pin "25") (pinfunction "A6_25") (pintype "passive"))
    )
    (net (code "55") (name "unconnected-(A1-A7-Pad26)") (class "Default")
      (node (ref "A1") (pin "26") (pinfunction "A7_26") (pintype "passive"))
    )
    (net (code "56") (name "unconnected-(A1-REF-Pad18)") (class "Default")
      (node (ref "A1") (pin "18") (pinfunction "REF_18") (pintype "passive"))
    )
    (net (code "57") (name "unconnected-(A1-RST-Pad3)") (class "Default")
      (node (ref "A1") (pin "3") (pinfunction "RST_3") (pintype "passive"))
    )
    (net (code "58") (name "unconnected-(A1-RST-Pad28)") (class "Default")
      (node (ref "A1") (pin "28") (pinfunction "RST_28") (pintype "passive"))
    )
    (net (code "59") (name "unconnected-(A1-RXD-Pad2)") (class "Default")
      (node (ref "A1") (pin "2") (pinfunction "RXD_2") (pintype "passive"))
    )
    (net (code "60") (name "unconnected-(A1-TX1-Pad1)") (class "Default")
      (node (ref "A1") (pin "1") (pinfunction "TX1_1") (pintype "passive"))
    )
    (net (code "61") (name "unconnected-(A1-VIN-Pad30)") (class "Default")
      (node (ref "A1") (pin "30") (pinfunction "VIN_30") (pintype "passive"))
    )
    (net (code "62") (name "unconnected-(J1-Pad2)") (class "Default")
      (node (ref "J1") (pin "2") (pinfunction "2_2") (pintype "passive"))
    )
    (net (code "63") (name "unconnected-(J6-Pad2)") (class "Default")
      (node (ref "J6") (pin "2") (pinfunction "2_2") (pintype "passive"))
    )
    (net (code "64") (name "unconnected-(J7-Pad2)") (class "Default")
      (node (ref "J7") (pin "2") (pinfunction "2_2") (pintype "passive"))
    )
    (net (code "65") (name "unconnected-(J8-Pad2)") (class "Default")
      (node (ref "J8") (pin "2") (pinfunction "2_2") (pintype "passive"))
    )
    (net (code "66") (name "unconnected-(J9-Pad2)") (class "Default")
      (node (ref "J9") (pin "2") (pinfunction "2_2") (pintype "passive"))
    )
    (net (code "67") (name "unconnected-(J10-Pad2)") (class "Default")
      (node (ref "J10") (pin "2") (pinfunction "2_2") (pintype "passive"))
    )
    (net (code "68") (name "unconnected-(J11-Pad2)") (class "Default")
      (node (ref "J11") (pin "2") (pinfunction "2_2") (pintype "passive"))
    )
    (net (code "69") (name "unconnected-(J12-Pad2)") (class "Default")
      (node (ref "J12") (pin "2") (pinfunction "2_2") (pintype "passive"))
    )
    (net (code "70") (name "unconnected-(J13-Pad2)") (class "Default")
      (node (ref "J13") (pin "2") (pinfunction "2_2") (pintype "passive"))
    )
    (net (code "71") (name "unconnected-(J14-Pad2)") (class "Default")
      (node (ref "J14") (pin "2") (pinfunction "2_2") (pintype "passive"))
    )
    (net (code "72") (name "unconnected-(K1-Pad2)") (class "Default")
      (node (ref "K1") (pin "2") (pinfunction "2_2") (pintype "passive"))
    )
    (net (code "73") (name "unconnected-(K1-Pad7)") (class "Default")
      (node (ref "K1") (pin "7") (pinfunction "7_7") (pintype "passive"))
    )
    (net (code "74") (name "unconnected-(K2-Pad2)") (class "Default")
      (node (ref "K2") (pin "2") (pinfunction "2_2") (pintype "passive"))
    )
    (net (code "75") (name "unconnected-(K2-Pad7)") (class "Default")
      (node (ref "K2") (pin "7") (pinfunction "7_7") (pintype "passive"))
    )
    (net (code "76") (name "unconnected-(K3-PadNC)") (class "Default")
      (node (ref "K3") (pin "NC") (pinfunction "NC_NC") (pintype "passive"))
    )
  )
)
